# outdoor.net
KiCad netlist of a schematic drawn in EAGLE
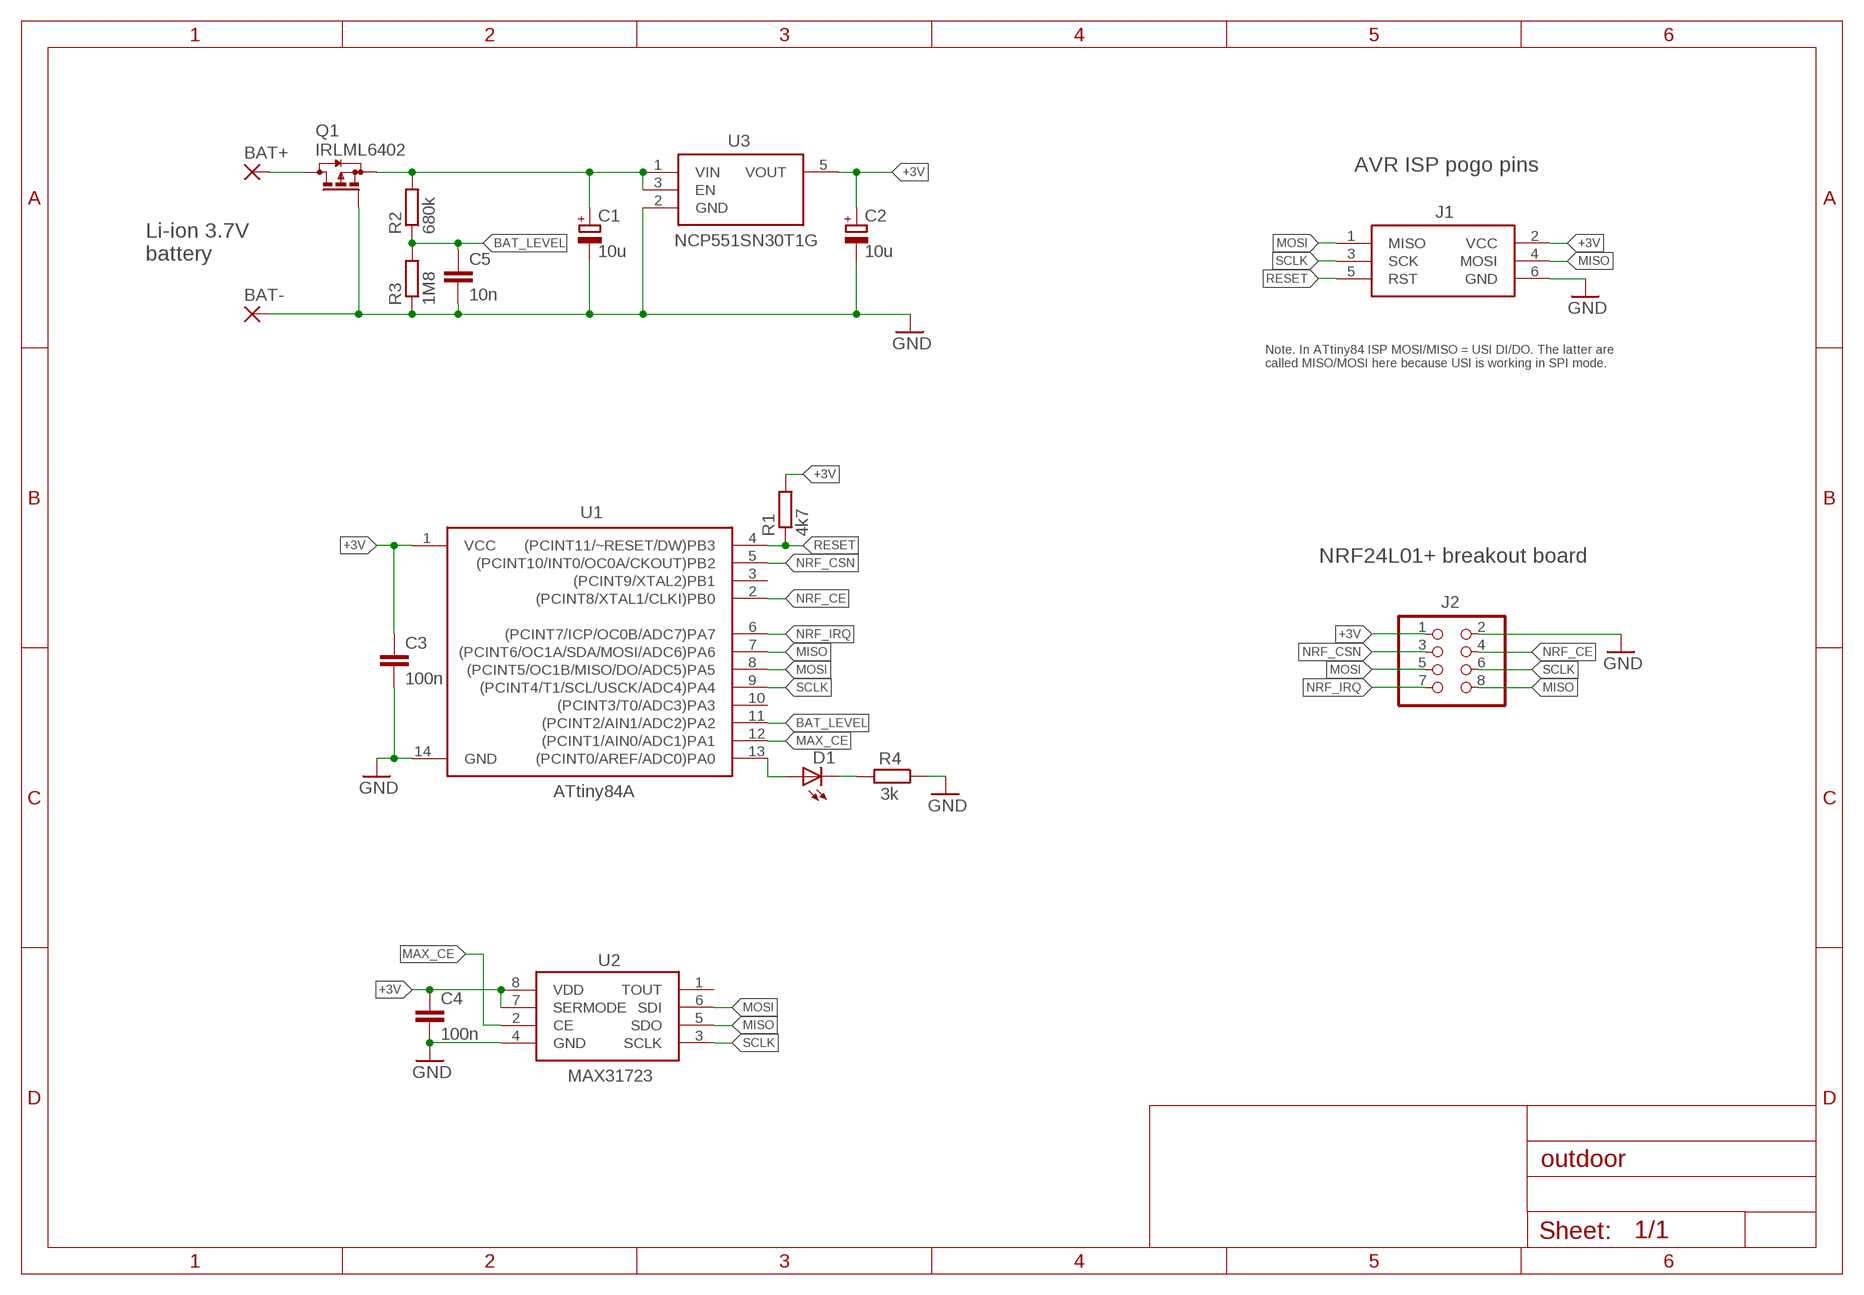
[diagram p0: schematic, sheet 1]

(export (version "E")
  (design (tool "Eeschema 10.0.6"))
  (components
    (comp (ref "BAT+")
      (value "2,54/1,0")
      (footprint "eagle-import:2,54_1,0")
      (libsource (lib "eagle-import") (part "2,54/1,0"))
    )
    (comp (ref "BAT-")
      (value "2,54/1,0")
      (footprint "eagle-import:2,54_1,0")
      (libsource (lib "eagle-import") (part "2,54/1,0"))
    )
    (comp (ref "C1")
      (value "10u")
      (footprint "eagle-import:CT3216")
      (libsource (lib "eagle-import") (part "CPOL-EUCT3216"))
    )
    (comp (ref "C2")
      (value "10u")
      (footprint "eagle-import:CT3216")
      (libsource (lib "eagle-import") (part "CPOL-EUCT3216"))
    )
    (comp (ref "C3")
      (value "100n")
      (footprint "eagle-import:C0805")
      (libsource (lib "eagle-import") (part "C-EUC0805"))
    )
    (comp (ref "C4")
      (value "100n")
      (footprint "eagle-import:C0805")
      (libsource (lib "eagle-import") (part "C-EUC0805"))
    )
    (comp (ref "C5")
      (value "10n")
      (footprint "eagle-import:C0805")
      (libsource (lib "eagle-import") (part "C-EUC0805"))
    )
    (comp (ref "D1")
      (value "LEDSMT1206")
      (footprint "eagle-import:1206")
      (libsource (lib "eagle-import") (part "LEDSMT1206"))
    )
    (comp (ref "J1")
      (value "POGO_AVR_ISP6")
      (footprint "eagle-import:POGO_AVR_ISP6")
      (libsource (lib "eagle-import") (part "POGO_AVR_ISP6"))
    )
    (comp (ref "J2")
      (value "PINHD-2X4")
      (footprint "eagle-import:2X04")
      (libsource (lib "eagle-import") (part "PINHD-2X4"))
    )
    (comp (ref "Q1")
      (value "IRLML6402")
      (footprint "eagle-import:SOT23")
      (libsource (lib "eagle-import") (part "BSS84"))
    )
    (comp (ref "R1")
      (value "4k7")
      (footprint "eagle-import:R0805")
      (libsource (lib "eagle-import") (part "R-EU_R0805"))
    )
    (comp (ref "R2")
      (value "680k")
      (footprint "eagle-import:R0805")
      (libsource (lib "eagle-import") (part "R-EU_R0805"))
    )
    (comp (ref "R3")
      (value "1M8")
      (footprint "eagle-import:R0805")
      (libsource (lib "eagle-import") (part "R-EU_R0805"))
    )
    (comp (ref "R4")
      (value "3k")
      (footprint "eagle-import:R0805")
      (libsource (lib "eagle-import") (part "R-EU_R0805"))
    )
    (comp (ref "U1")
      (value "ATtiny84A")
      (footprint "eagle-import:SO14")
      (libsource (lib "eagle-import") (part "ATTINY84"))
    )
    (comp (ref "U2")
      (value "MAX31723")
      (footprint "eagle-import:UMAX8")
      (libsource (lib "eagle-import") (part "MAX31722"))
    )
    (comp (ref "U3")
      (value "NCP551SN30T1G")
      (footprint "eagle-import:SOT23-5")
      (libsource (lib "eagle-import") (part "NCP551"))
    )
  )
  (nets
    (net (code "1") (name "+3V") (class "Default")
      (node (ref "C2") (pin "+") (pinfunction "+_+") (pintype "passive"))
      (node (ref "C3") (pin "1") (pinfunction "1_1") (pintype "passive"))
      (node (ref "C4") (pin "1") (pinfunction "1_1") (pintype "passive"))
      (node (ref "J1") (pin "2") (pinfunction "VCC_2") (pintype "bidirectional"))
      (node (ref "J2") (pin "1") (pinfunction "1_1") (pintype "passive"))
      (node (ref "R1") (pin "2") (pinfunction "2_2") (pintype "passive"))
      (node (ref "U1") (pin "1") (pinfunction "VCC_1") (pintype "bidirectional"))
      (node (ref "U2") (pin "7") (pinfunction "SERMODE_7") (pintype "bidirectional"))
      (node (ref "U2") (pin "8") (pinfunction "VDD_8") (pintype "bidirectional"))
      (node (ref "U3") (pin "5") (pinfunction "VOUT_5") (pintype "bidirectional"))
    )
    (net (code "2") (name "BAT_LEVEL") (class "Default")
      (node (ref "C5") (pin "1") (pinfunction "1_1") (pintype "passive"))
      (node (ref "R2") (pin "1") (pinfunction "1_1") (pintype "passive"))
      (node (ref "R3") (pin "2") (pinfunction "2_2") (pintype "passive"))
      (node (ref "U1") (pin "11") (pinfunction "(PCINT2/AIN1/ADC2)PA2_11") (pintype "bidirectional"))
    )
    (net (code "3") (name "GND") (class "Default")
      (node (ref "BAT-") (pin "1") (pinfunction "P_1") (pintype "passive"))
      (node (ref "C1") (pin "-") (pinfunction "-_-") (pintype "passive"))
      (node (ref "C2") (pin "-") (pinfunction "-_-") (pintype "passive"))
      (node (ref "C3") (pin "2") (pinfunction "2_2") (pintype "passive"))
      (node (ref "C4") (pin "2") (pinfunction "2_2") (pintype "passive"))
      (node (ref "C5") (pin "2") (pinfunction "2_2") (pintype "passive"))
      (node (ref "J1") (pin "6") (pinfunction "GND_6") (pintype "bidirectional"))
      (node (ref "J2") (pin "2") (pinfunction "2_2") (pintype "passive"))
      (node (ref "Q1") (pin "1") (pinfunction "G_1") (pintype "passive"))
      (node (ref "R3") (pin "1") (pinfunction "1_1") (pintype "passive"))
      (node (ref "R4") (pin "1") (pinfunction "1_1") (pintype "passive"))
      (node (ref "U1") (pin "14") (pinfunction "GND_14") (pintype "bidirectional"))
      (node (ref "U2") (pin "4") (pinfunction "GND_4") (pintype "bidirectional"))
      (node (ref "U3") (pin "2") (pinfunction "GND_2") (pintype "bidirectional"))
    )
    (net (code "4") (name "MAX_CE") (class "Default")
      (node (ref "U1") (pin "12") (pinfunction "(PCINT1/AIN0/ADC1)PA1_12") (pintype "bidirectional"))
      (node (ref "U2") (pin "2") (pinfunction "CE_2") (pintype "bidirectional"))
    )
    (net (code "5") (name "MISO") (class "Default")
      (node (ref "J1") (pin "4") (pinfunction "MOSI_4") (pintype "bidirectional"))
      (node (ref "J2") (pin "8") (pinfunction "8_8") (pintype "passive"))
      (node (ref "U1") (pin "7") (pinfunction "(PCINT6/OC1A/SDA/MOSI/ADC6)PA6_7") (pintype "bidirectional"))
      (node (ref "U2") (pin "5") (pinfunction "SDO_5") (pintype "bidirectional"))
    )
    (net (code "6") (name "MOSI") (class "Default")
      (node (ref "J1") (pin "1") (pinfunction "MISO_1") (pintype "bidirectional"))
      (node (ref "J2") (pin "5") (pinfunction "5_5") (pintype "passive"))
      (node (ref "U1") (pin "8") (pinfunction "(PCINT5/OC1B/MISO/DO/ADC5)PA5_8") (pintype "bidirectional"))
      (node (ref "U2") (pin "6") (pinfunction "SDI_6") (pintype "bidirectional"))
    )
    (net (code "7") (name "NRF_CE") (class "Default")
      (node (ref "J2") (pin "4") (pinfunction "4_4") (pintype "passive"))
      (node (ref "U1") (pin "2") (pinfunction "(PCINT8/XTAL1/CLKI)PB0_2") (pintype "bidirectional"))
    )
    (net (code "8") (name "NRF_CSN") (class "Default")
      (node (ref "J2") (pin "3") (pinfunction "3_3") (pintype "passive"))
      (node (ref "U1") (pin "5") (pinfunction "(PCINT10/INT0/OC0A/CKOUT)PB2_5") (pintype "bidirectional"))
    )
    (net (code "9") (name "NRF_IRQ") (class "Default")
      (node (ref "J2") (pin "7") (pinfunction "7_7") (pintype "passive"))
      (node (ref "U1") (pin "6") (pinfunction "(PCINT7/ICP/OC0B/ADC7)PA7_6") (pintype "bidirectional"))
    )
    (net (code "10") (name "Net-(BAT+-P)") (class "Default")
      (node (ref "BAT+") (pin "1") (pinfunction "P_1") (pintype "passive"))
      (node (ref "Q1") (pin "3") (pinfunction "D_3") (pintype "passive"))
    )
    (net (code "11") (name "Net-(D1-PadC)") (class "Default")
      (node (ref "D1") (pin "C") (pinfunction "C_C") (pintype "passive"))
      (node (ref "R4") (pin "2") (pinfunction "2_2") (pintype "passive"))
    )
    (net (code "12") (name "Net-(Q1-S)") (class "Default")
      (node (ref "C1") (pin "+") (pinfunction "+_+") (pintype "passive"))
      (node (ref "Q1") (pin "2") (pinfunction "S_2") (pintype "passive"))
      (node (ref "R2") (pin "2") (pinfunction "2_2") (pintype "passive"))
      (node (ref "U3") (pin "1") (pinfunction "VIN_1") (pintype "bidirectional"))
      (node (ref "U3") (pin "3") (pinfunction "EN_3") (pintype "bidirectional"))
    )
    (net (code "13") (name "Net-(U1-(PCINT0{slash}AREF{slash}ADC0)PA0)") (class "Default")
      (node (ref "D1") (pin "A") (pinfunction "A_A") (pintype "passive"))
      (node (ref "U1") (pin "13") (pinfunction "(PCINT0/AREF/ADC0)PA0_13") (pintype "bidirectional"))
    )
    (net (code "14") (name "RESET") (class "Default")
      (node (ref "J1") (pin "5") (pinfunction "RST_5") (pintype "bidirectional"))
      (node (ref "R1") (pin "1") (pinfunction "1_1") (pintype "passive"))
      (node (ref "U1") (pin "4") (pinfunction "(PCINT11/~{RESET/DW})PB3_4") (pintype "bidirectional"))
    )
    (net (code "15") (name "SCLK") (class "Default")
      (node (ref "J1") (pin "3") (pinfunction "SCK_3") (pintype "bidirectional"))
      (node (ref "J2") (pin "6") (pinfunction "6_6") (pintype "passive"))
      (node (ref "U1") (pin "9") (pinfunction "(PCINT4/T1/SCL/USCK/ADC4)PA4_9") (pintype "bidirectional"))
      (node (ref "U2") (pin "3") (pinfunction "SCLK_3") (pintype "bidirectional"))
    )
    (net (code "16") (name "unconnected-(U1-(PCINT3{slash}T0{slash}ADC3)PA3-Pad10)") (class "Default")
      (node (ref "U1") (pin "10") (pinfunction "(PCINT3/T0/ADC3)PA3_10") (pintype "bidirectional"))
    )
    (net (code "17") (name "unconnected-(U1-(PCINT9{slash}XTAL2)PB1-Pad3)") (class "Default")
      (node (ref "U1") (pin "3") (pinfunction "(PCINT9/XTAL2)PB1_3") (pintype "bidirectional"))
    )
    (net (code "18") (name "unconnected-(U2-TOUT-Pad1)") (class "Default")
      (node (ref "U2") (pin "1") (pinfunction "TOUT_1") (pintype "bidirectional"))
    )
  )
)
